# board_autorouted_2_layers-v2.net
KiCad netlist of a schematic drawn in EAGLE
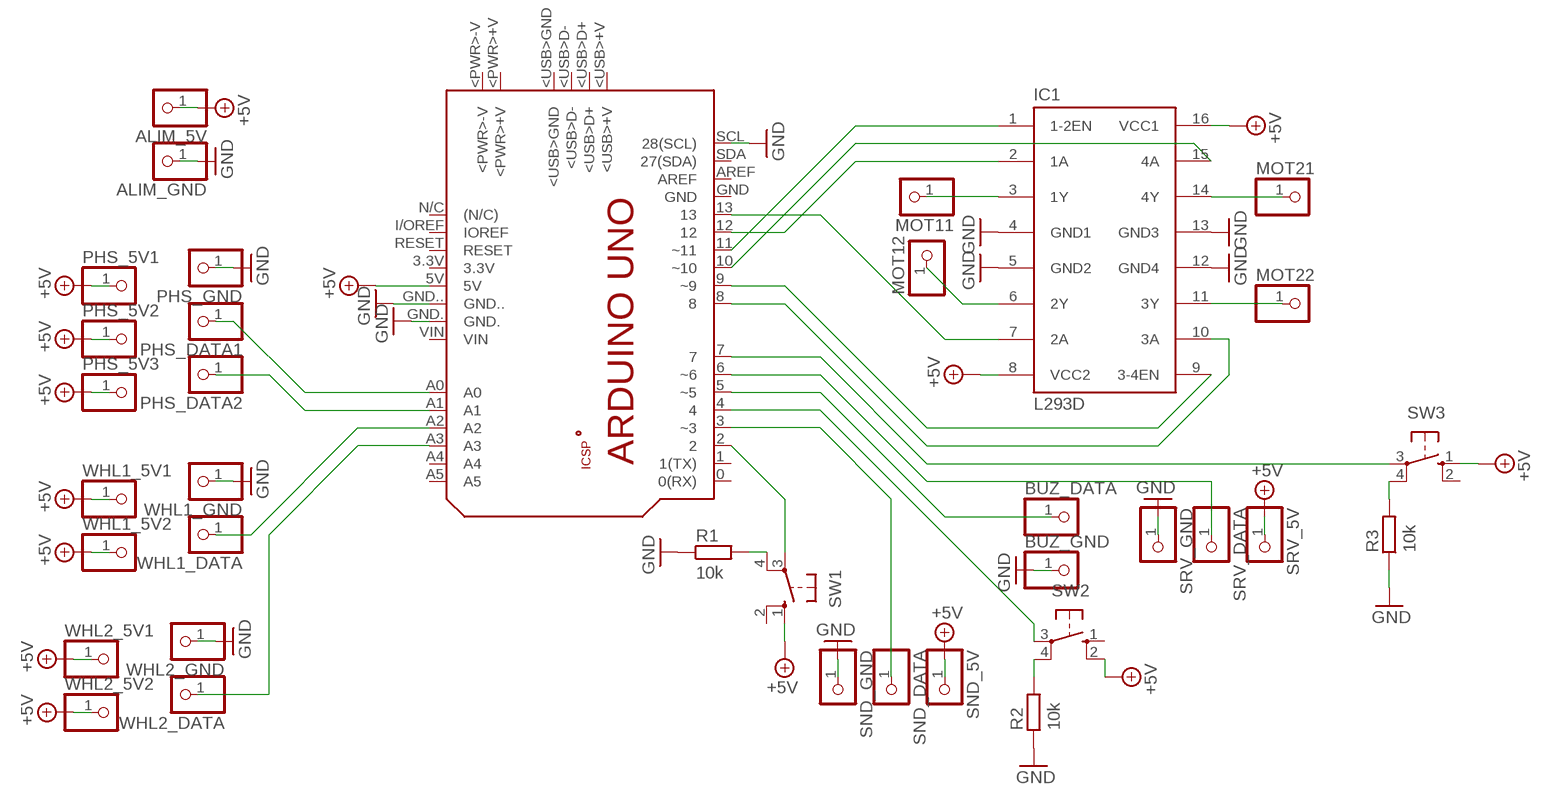
[diagram p0: schematic, sheet 1]

(export (version "E")
  (design (tool "Eeschema 10.0.6"))
  (components
    (comp (ref "ALIM_5V")
      (value "PINHD-1X1")
      (footprint "eagle-import:1X01")
      (libsource (lib "eagle-import") (part "PINHD-1X1"))
    )
    (comp (ref "ALIM_GND")
      (value "PINHD-1X1")
      (footprint "eagle-import:1X01")
      (libsource (lib "eagle-import") (part "PINHD-1X1"))
    )
    (comp (ref "BUZ_DATA")
      (value "PINHD-1X1")
      (footprint "eagle-import:1X01")
      (libsource (lib "eagle-import") (part "PINHD-1X1"))
    )
    (comp (ref "BUZ_GND")
      (value "PINHD-1X1")
      (footprint "eagle-import:1X01")
      (libsource (lib "eagle-import") (part "PINHD-1X1"))
    )
    (comp (ref "IC1")
      (value "L293D")
      (footprint "eagle-import:DIL16")
      (libsource (lib "eagle-import") (part "L293D"))
    )
    (comp (ref "MOT11")
      (value "PINHD-1X1")
      (footprint "eagle-import:1X01")
      (libsource (lib "eagle-import") (part "PINHD-1X1"))
    )
    (comp (ref "MOT12")
      (value "PINHD-1X1")
      (footprint "eagle-import:1X01")
      (libsource (lib "eagle-import") (part "PINHD-1X1"))
    )
    (comp (ref "MOT21")
      (value "PINHD-1X1")
      (footprint "eagle-import:1X01")
      (libsource (lib "eagle-import") (part "PINHD-1X1"))
    )
    (comp (ref "MOT22")
      (value "PINHD-1X1")
      (footprint "eagle-import:1X01")
      (libsource (lib "eagle-import") (part "PINHD-1X1"))
    )
    (comp (ref "PCB1")
      (value "ARDUINO_UNO")
      (footprint "eagle-import:ARDUINO_UNO")
      (libsource (lib "eagle-import") (part "ARDUINO_UNO"))
    )
    (comp (ref "PHS_5V1")
      (value "PINHD-1X1")
      (footprint "eagle-import:1X01")
      (libsource (lib "eagle-import") (part "PINHD-1X1"))
    )
    (comp (ref "PHS_5V2")
      (value "PINHD-1X1")
      (footprint "eagle-import:1X01")
      (libsource (lib "eagle-import") (part "PINHD-1X1"))
    )
    (comp (ref "PHS_5V3")
      (value "PINHD-1X1")
      (footprint "eagle-import:1X01")
      (libsource (lib "eagle-import") (part "PINHD-1X1"))
    )
    (comp (ref "PHS_DATA1")
      (value "PINHD-1X1")
      (footprint "eagle-import:1X01")
      (libsource (lib "eagle-import") (part "PINHD-1X1"))
    )
    (comp (ref "PHS_DATA2")
      (value "PINHD-1X1")
      (footprint "eagle-import:1X01")
      (libsource (lib "eagle-import") (part "PINHD-1X1"))
    )
    (comp (ref "PHS_GND")
      (value "PINHD-1X1")
      (footprint "eagle-import:1X01")
      (libsource (lib "eagle-import") (part "PINHD-1X1"))
    )
    (comp (ref "R1")
      (value "10k")
      (footprint "eagle-import:R0603")
      (libsource (lib "eagle-import") (part "RESISTOR"))
    )
    (comp (ref "R2")
      (value "10k")
      (footprint "eagle-import:R0603")
      (libsource (lib "eagle-import") (part "RESISTOR"))
    )
    (comp (ref "R3")
      (value "10k")
      (footprint "eagle-import:R0603")
      (libsource (lib "eagle-import") (part "RESISTOR"))
    )
    (comp (ref "SND_5V")
      (value "PINHD-1X1")
      (footprint "eagle-import:1X01")
      (libsource (lib "eagle-import") (part "PINHD-1X1"))
    )
    (comp (ref "SND_DATA")
      (value "PINHD-1X1")
      (footprint "eagle-import:1X01")
      (libsource (lib "eagle-import") (part "PINHD-1X1"))
    )
    (comp (ref "SND_GND")
      (value "PINHD-1X1")
      (footprint "eagle-import:1X01")
      (libsource (lib "eagle-import") (part "PINHD-1X1"))
    )
    (comp (ref "SRV_5V")
      (value "PINHD-1X1")
      (footprint "eagle-import:1X01")
      (libsource (lib "eagle-import") (part "PINHD-1X1"))
    )
    (comp (ref "SRV_DATA")
      (value "PINHD-1X1")
      (footprint "eagle-import:1X01")
      (libsource (lib "eagle-import") (part "PINHD-1X1"))
    )
    (comp (ref "SRV_GND")
      (value "PINHD-1X1")
      (footprint "eagle-import:1X01")
      (libsource (lib "eagle-import") (part "PINHD-1X1"))
    )
    (comp (ref "SW1")
      (value "40-XX")
      (footprint "eagle-import:B3F-40XX")
      (fields (field (name "MF") "OMRON COMPONENTS USA") (field (name "MPN") "B3F-4000"))
      (libsource (lib "eagle-import") (part "40-XX"))
    )
    (comp (ref "SW2")
      (value "40-XX")
      (footprint "eagle-import:B3F-40XX")
      (fields (field (name "MF") "OMRON COMPONENTS USA") (field (name "MPN") "B3F-4000"))
      (libsource (lib "eagle-import") (part "40-XX"))
    )
    (comp (ref "SW3")
      (value "40-XX")
      (footprint "eagle-import:B3F-40XX")
      (fields (field (name "MF") "OMRON COMPONENTS USA") (field (name "MPN") "B3F-4000"))
      (libsource (lib "eagle-import") (part "40-XX"))
    )
    (comp (ref "WHL1_5V1")
      (value "PINHD-1X1")
      (footprint "eagle-import:1X01")
      (libsource (lib "eagle-import") (part "PINHD-1X1"))
    )
    (comp (ref "WHL1_5V2")
      (value "PINHD-1X1")
      (footprint "eagle-import:1X01")
      (libsource (lib "eagle-import") (part "PINHD-1X1"))
    )
    (comp (ref "WHL1_DATA")
      (value "PINHD-1X1")
      (footprint "eagle-import:1X01")
      (libsource (lib "eagle-import") (part "PINHD-1X1"))
    )
    (comp (ref "WHL1_GND")
      (value "PINHD-1X1")
      (footprint "eagle-import:1X01")
      (libsource (lib "eagle-import") (part "PINHD-1X1"))
    )
    (comp (ref "WHL2_5V1")
      (value "PINHD-1X1")
      (footprint "eagle-import:1X01")
      (libsource (lib "eagle-import") (part "PINHD-1X1"))
    )
    (comp (ref "WHL2_5V2")
      (value "PINHD-1X1")
      (footprint "eagle-import:1X01")
      (libsource (lib "eagle-import") (part "PINHD-1X1"))
    )
    (comp (ref "WHL2_DATA")
      (value "PINHD-1X1")
      (footprint "eagle-import:1X01")
      (libsource (lib "eagle-import") (part "PINHD-1X1"))
    )
    (comp (ref "WHL2_GND")
      (value "PINHD-1X1")
      (footprint "eagle-import:1X01")
      (libsource (lib "eagle-import") (part "PINHD-1X1"))
    )
  )
  (nets
    (net (code "1") (name "+5V") (class "Default")
      (node (ref "ALIM_5V") (pin "1") (pinfunction "1_1") (pintype "passive"))
      (node (ref "IC1") (pin "16") (pinfunction "VCC1_16") (pintype "power_in"))
      (node (ref "IC1") (pin "8") (pinfunction "VCC2_8") (pintype "power_in"))
      (node (ref "PCB1") (pin "5V") (pinfunction "5V_5V") (pintype "bidirectional"))
      (node (ref "PHS_5V1") (pin "1") (pinfunction "1_1") (pintype "passive"))
      (node (ref "PHS_5V2") (pin "1") (pinfunction "1_1") (pintype "passive"))
      (node (ref "PHS_5V3") (pin "1") (pinfunction "1_1") (pintype "passive"))
      (node (ref "SND_5V") (pin "1") (pinfunction "1_1") (pintype "passive"))
      (node (ref "SRV_5V") (pin "1") (pinfunction "1_1") (pintype "passive"))
      (node (ref "SW1") (pin "1") (pinfunction "S_1") (pintype "passive"))
      (node (ref "SW2") (pin "2") (pinfunction "S1_2") (pintype "passive"))
      (node (ref "SW3") (pin "1") (pinfunction "S_1") (pintype "passive"))
      (node (ref "WHL1_5V1") (pin "1") (pinfunction "1_1") (pintype "passive"))
      (node (ref "WHL1_5V2") (pin "1") (pinfunction "1_1") (pintype "passive"))
      (node (ref "WHL2_5V1") (pin "1") (pinfunction "1_1") (pintype "passive"))
      (node (ref "WHL2_5V2") (pin "1") (pinfunction "1_1") (pintype "passive"))
    )
    (net (code "2") (name "GND") (class "Default")
      (node (ref "ALIM_GND") (pin "1") (pinfunction "1_1") (pintype "passive"))
      (node (ref "BUZ_GND") (pin "1") (pinfunction "1_1") (pintype "passive"))
      (node (ref "IC1") (pin "12") (pinfunction "GND4_12") (pintype "power_in"))
      (node (ref "IC1") (pin "13") (pinfunction "GND3_13") (pintype "power_in"))
      (node (ref "IC1") (pin "4") (pinfunction "GND1_4") (pintype "power_in"))
      (node (ref "IC1") (pin "5") (pinfunction "GND2_5") (pintype "power_in"))
      (node (ref "PCB1") (pin "GND.") (pinfunction "GND._GND.") (pintype "bidirectional"))
      (node (ref "PCB1") (pin "GND..") (pinfunction "GND.._GND..") (pintype "bidirectional"))
      (node (ref "PCB1") (pin "SCL") (pinfunction "28(SCL)_SCL") (pintype "bidirectional"))
      (node (ref "PHS_GND") (pin "1") (pinfunction "1_1") (pintype "passive"))
      (node (ref "R1") (pin "1") (pinfunction "1_1") (pintype "passive"))
      (node (ref "R2") (pin "1") (pinfunction "1_1") (pintype "passive"))
      (node (ref "R3") (pin "1") (pinfunction "1_1") (pintype "passive"))
      (node (ref "SND_GND") (pin "1") (pinfunction "1_1") (pintype "passive"))
      (node (ref "SRV_GND") (pin "1") (pinfunction "1_1") (pintype "passive"))
      (node (ref "WHL1_GND") (pin "1") (pinfunction "1_1") (pintype "passive"))
      (node (ref "WHL2_GND") (pin "1") (pinfunction "1_1") (pintype "passive"))
    )
    (net (code "3") (name "Net-(IC1-1-2EN)") (class "Default")
      (node (ref "IC1") (pin "1") (pinfunction "1-2EN_1") (pintype "input"))
      (node (ref "PCB1") (pin "11") (pinfunction "~{11}_11") (pintype "bidirectional"))
    )
    (net (code "4") (name "Net-(IC1-1A)") (class "Default")
      (node (ref "IC1") (pin "2") (pinfunction "1A_2") (pintype "input"))
      (node (ref "PCB1") (pin "12") (pinfunction "12_12") (pintype "bidirectional"))
    )
    (net (code "5") (name "Net-(IC1-1Y)") (class "Default")
      (node (ref "IC1") (pin "3") (pinfunction "1Y_3") (pintype "output"))
      (node (ref "MOT11") (pin "1") (pinfunction "1_1") (pintype "passive"))
    )
    (net (code "6") (name "Net-(IC1-2A)") (class "Default")
      (node (ref "IC1") (pin "7") (pinfunction "2A_7") (pintype "input"))
      (node (ref "PCB1") (pin "13") (pinfunction "13_13") (pintype "bidirectional"))
    )
    (net (code "7") (name "Net-(IC1-2Y)") (class "Default")
      (node (ref "IC1") (pin "6") (pinfunction "2Y_6") (pintype "output"))
      (node (ref "MOT12") (pin "1") (pinfunction "1_1") (pintype "passive"))
    )
    (net (code "8") (name "Net-(IC1-3-4EN)") (class "Default")
      (node (ref "IC1") (pin "9") (pinfunction "3-4EN_9") (pintype "input"))
      (node (ref "PCB1") (pin "9") (pinfunction "~{9}_9") (pintype "bidirectional"))
    )
    (net (code "9") (name "Net-(IC1-3A)") (class "Default")
      (node (ref "IC1") (pin "10") (pinfunction "3A_10") (pintype "input"))
      (node (ref "PCB1") (pin "8") (pinfunction "8_8") (pintype "bidirectional"))
    )
    (net (code "10") (name "Net-(IC1-3Y)") (class "Default")
      (node (ref "IC1") (pin "11") (pinfunction "3Y_11") (pintype "output"))
      (node (ref "MOT22") (pin "1") (pinfunction "1_1") (pintype "passive"))
    )
    (net (code "11") (name "Net-(IC1-4A)") (class "Default")
      (node (ref "IC1") (pin "15") (pinfunction "4A_15") (pintype "input"))
      (node (ref "PCB1") (pin "10") (pinfunction "~{10}_10") (pintype "bidirectional"))
    )
    (net (code "12") (name "Net-(IC1-4Y)") (class "Default")
      (node (ref "IC1") (pin "14") (pinfunction "4Y_14") (pintype "output"))
      (node (ref "MOT21") (pin "1") (pinfunction "1_1") (pintype "passive"))
    )
    (net (code "13") (name "Net-(PCB1-PadA0)") (class "Default")
      (node (ref "PCB1") (pin "A0") (pinfunction "A0_A0") (pintype "bidirectional"))
      (node (ref "PHS_DATA1") (pin "1") (pinfunction "1_1") (pintype "passive"))
    )
    (net (code "14") (name "Net-(PCB1-PadA1)") (class "Default")
      (node (ref "PCB1") (pin "A1") (pinfunction "A1_A1") (pintype "bidirectional"))
      (node (ref "PHS_DATA2") (pin "1") (pinfunction "1_1") (pintype "passive"))
    )
    (net (code "15") (name "Net-(PCB1-PadA2)") (class "Default")
      (node (ref "PCB1") (pin "A2") (pinfunction "A2_A2") (pintype "bidirectional"))
      (node (ref "WHL1_DATA") (pin "1") (pinfunction "1_1") (pintype "passive"))
    )
    (net (code "16") (name "Net-(PCB1-PadA3)") (class "Default")
      (node (ref "PCB1") (pin "A3") (pinfunction "A3_A3") (pintype "bidirectional"))
      (node (ref "WHL2_DATA") (pin "1") (pinfunction "1_1") (pintype "passive"))
    )
    (net (code "17") (name "Net-(PCB1-~{3})") (class "Default")
      (node (ref "PCB1") (pin "3") (pinfunction "~{3}_3") (pintype "bidirectional"))
      (node (ref "SND_DATA") (pin "1") (pinfunction "1_1") (pintype "passive"))
    )
    (net (code "18") (name "Net-(PCB1-~{5})") (class "Default")
      (node (ref "BUZ_DATA") (pin "1") (pinfunction "1_1") (pintype "passive"))
      (node (ref "PCB1") (pin "5") (pinfunction "~{5}_5") (pintype "bidirectional"))
    )
    (net (code "19") (name "Net-(PCB1-~{6})") (class "Default")
      (node (ref "PCB1") (pin "6") (pinfunction "~{6}_6") (pintype "bidirectional"))
      (node (ref "SRV_DATA") (pin "1") (pinfunction "1_1") (pintype "passive"))
    )
    (net (code "20") (name "Net-(SW1-P)") (class "Default")
      (node (ref "PCB1") (pin "2") (pinfunction "2_2") (pintype "bidirectional"))
      (node (ref "SW1") (pin "3") (pinfunction "P_3") (pintype "passive"))
    )
    (net (code "21") (name "Net-(SW1-P1)") (class "Default")
      (node (ref "R1") (pin "2") (pinfunction "2_2") (pintype "passive"))
      (node (ref "SW1") (pin "4") (pinfunction "P1_4") (pintype "passive"))
    )
    (net (code "22") (name "Net-(SW2-P)") (class "Default")
      (node (ref "PCB1") (pin "4") (pinfunction "4_4") (pintype "bidirectional"))
      (node (ref "SW2") (pin "3") (pinfunction "P_3") (pintype "passive"))
    )
    (net (code "23") (name "Net-(SW2-P1)") (class "Default")
      (node (ref "R2") (pin "2") (pinfunction "2_2") (pintype "passive"))
      (node (ref "SW2") (pin "4") (pinfunction "P1_4") (pintype "passive"))
    )
    (net (code "24") (name "Net-(SW3-P)") (class "Default")
      (node (ref "PCB1") (pin "7") (pinfunction "7_7") (pintype "bidirectional"))
      (node (ref "SW3") (pin "3") (pinfunction "P_3") (pintype "passive"))
    )
    (net (code "25") (name "Net-(SW3-P1)") (class "Default")
      (node (ref "R3") (pin "2") (pinfunction "2_2") (pintype "passive"))
      (node (ref "SW3") (pin "4") (pinfunction "P1_4") (pintype "passive"))
    )
    (net (code "26") (name "unconnected-(PCB1-(N{slash}C)-PadN{slash}C)") (class "Default")
      (node (ref "PCB1") (pin "N/C") (pinfunction "(N/C)_N/C") (pintype "bidirectional"))
    )
    (net (code "27") (name "unconnected-(PCB1-0(RX)-Pad0)") (class "Default")
      (node (ref "PCB1") (pin "0") (pinfunction "0(RX)_0") (pintype "bidirectional"))
    )
    (net (code "28") (name "unconnected-(PCB1-1(TX)-Pad1)") (class "Default")
      (node (ref "PCB1") (pin "1") (pinfunction "1(TX)_1") (pintype "bidirectional"))
    )
    (net (code "29") (name "unconnected-(PCB1-27(SDA)-PadSDA)") (class "Default")
      (node (ref "PCB1") (pin "SDA") (pinfunction "27(SDA)_SDA") (pintype "bidirectional"))
    )
    (net (code "30") (name "unconnected-(PCB1-IOREF-PadI{slash}OREF)") (class "Default")
      (node (ref "PCB1") (pin "I/OREF") (pinfunction "IOREF_I/OREF") (pintype "bidirectional"))
    )
    (net (code "31") (name "unconnected-(PCB1-Pad+5V)") (class "Default")
      (node (ref "PCB1") (pin "+5V") (pinfunction "+5V_+5V") (pintype "bidirectional"))
    )
    (net (code "32") (name "unconnected-(PCB1-Pad3.3V)") (class "Default")
      (node (ref "PCB1") (pin "3.3V") (pinfunction "3.3V_3.3V") (pintype "bidirectional"))
    )
    (net (code "33") (name "unconnected-(PCB1-Pad<PWR>+V)") (class "Default")
      (node (ref "PCB1") (pin "<PWR>+V") (pinfunction "<PWR>+V_<PWR>+V") (pintype "bidirectional"))
    )
    (net (code "34") (name "unconnected-(PCB1-Pad<PWR>-V)") (class "Default")
      (node (ref "PCB1") (pin "<PWR>-V") (pinfunction "<PWR>-V_<PWR>-V") (pintype "bidirectional"))
    )
    (net (code "35") (name "unconnected-(PCB1-Pad<USB>+V)") (class "Default")
      (node (ref "PCB1") (pin "<USB>+V") (pinfunction "<USB>+V_<USB>+V") (pintype "bidirectional"))
    )
    (net (code "36") (name "unconnected-(PCB1-Pad<USB>D+)") (class "Default")
      (node (ref "PCB1") (pin "<USB>D+") (pinfunction "<USB>D+_<USB>D+") (pintype "bidirectional"))
    )
    (net (code "37") (name "unconnected-(PCB1-Pad<USB>D-)") (class "Default")
      (node (ref "PCB1") (pin "<USB>D-") (pinfunction "<USB>D-_<USB>D-") (pintype "bidirectional"))
    )
    (net (code "38") (name "unconnected-(PCB1-Pad<USB>GND)") (class "Default")
      (node (ref "PCB1") (pin "<USB>GND") (pinfunction "<USB>GND_<USB>GND") (pintype "bidirectional"))
    )
    (net (code "39") (name "unconnected-(PCB1-PadA4)") (class "Default")
      (node (ref "PCB1") (pin "A4") (pinfunction "A4_A4") (pintype "bidirectional"))
    )
    (net (code "40") (name "unconnected-(PCB1-PadA5)") (class "Default")
      (node (ref "PCB1") (pin "A5") (pinfunction "A5_A5") (pintype "bidirectional"))
    )
    (net (code "41") (name "unconnected-(PCB1-PadAREF)") (class "Default")
      (node (ref "PCB1") (pin "AREF") (pinfunction "AREF_AREF") (pintype "bidirectional"))
    )
    (net (code "42") (name "unconnected-(PCB1-PadGND)") (class "Default")
      (node (ref "PCB1") (pin "GND") (pinfunction "GND_GND") (pintype "bidirectional"))
    )
    (net (code "43") (name "unconnected-(PCB1-PadGND_)") (class "Default")
      (node (ref "PCB1") (pin "GND_") (pinfunction "GND__GND_") (pintype "bidirectional"))
    )
    (net (code "44") (name "unconnected-(PCB1-PadMISO)") (class "Default")
      (node (ref "PCB1") (pin "MISO") (pinfunction "MISO_MISO") (pintype "bidirectional"))
    )
    (net (code "45") (name "unconnected-(PCB1-PadMOSI)") (class "Default")
      (node (ref "PCB1") (pin "MOSI") (pinfunction "MOSI_MOSI") (pintype "bidirectional"))
    )
    (net (code "46") (name "unconnected-(PCB1-PadRESET)") (class "Default")
      (node (ref "PCB1") (pin "RESET") (pinfunction "RESET_RESET") (pintype "bidirectional"))
    )
    (net (code "47") (name "unconnected-(PCB1-PadRESET.)") (class "Default")
      (node (ref "PCB1") (pin "RESET.") (pinfunction "RESET._RESET.") (pintype "bidirectional"))
    )
    (net (code "48") (name "unconnected-(PCB1-PadSCK)") (class "Default")
      (node (ref "PCB1") (pin "SCK") (pinfunction "SCK_SCK") (pintype "bidirectional"))
    )
    (net (code "49") (name "unconnected-(PCB1-PadVIN)") (class "Default")
      (node (ref "PCB1") (pin "VIN") (pinfunction "VIN_VIN") (pintype "bidirectional"))
    )
    (net (code "50") (name "unconnected-(SW1-S1-Pad2)") (class "Default")
      (node (ref "SW1") (pin "2") (pinfunction "S1_2") (pintype "passive"))
    )
    (net (code "51") (name "unconnected-(SW2-S-Pad1)") (class "Default")
      (node (ref "SW2") (pin "1") (pinfunction "S_1") (pintype "passive"))
    )
    (net (code "52") (name "unconnected-(SW3-S1-Pad2)") (class "Default")
      (node (ref "SW3") (pin "2") (pinfunction "S1_2") (pintype "passive"))
    )
  )
)
